# H3_eMMC.net
KiCad netlist of a schematic drawn in Altium Designer
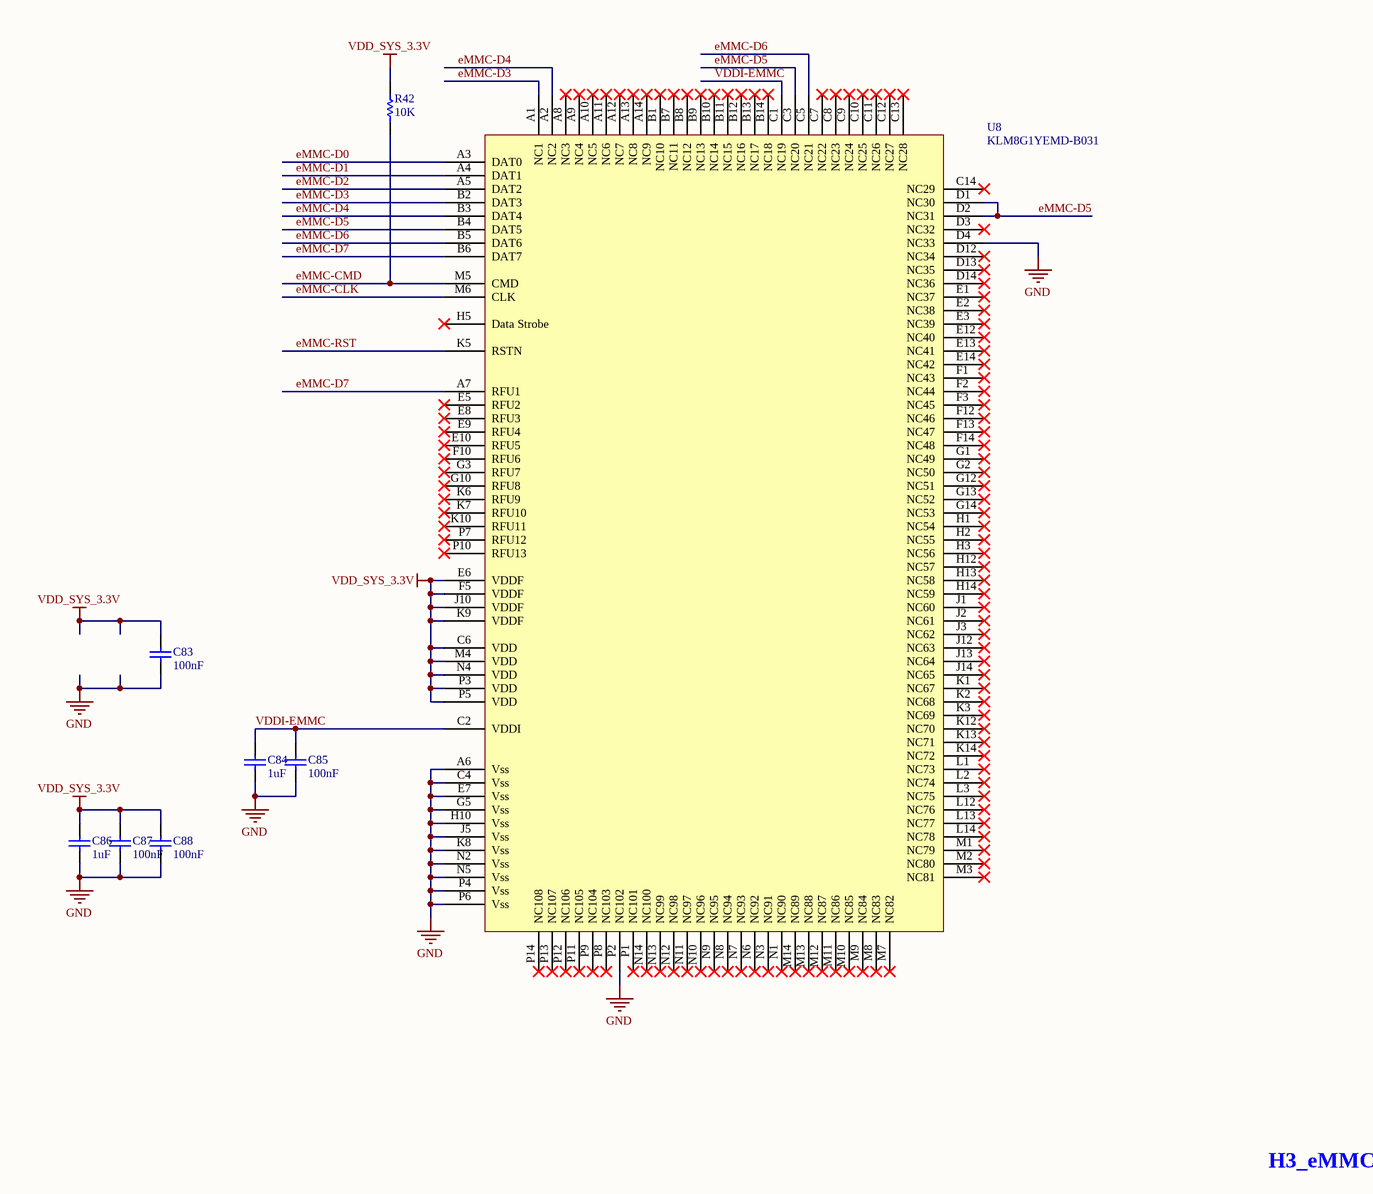
[diagram p0: H3_eMMC.SchDoc]

(export (version "E")
  (design (tool "Eeschema 10.0.6"))
  (components
    (comp (ref "C83")
      (value "100nF")
      (footprint "H3_Core:C0402")
      (description "电容")
      (fields (field (name "PUBLISHER") "Altium Limited"))
      (libsource (lib "Devices") (part "C0402"))
    )
    (comp (ref "C84")
      (value "1uF")
      (footprint "H3_Core:C0402")
      (description "电容")
      (fields (field (name "PUBLISHER") "Altium Limited"))
      (libsource (lib "Devices") (part "C0402"))
    )
    (comp (ref "C85")
      (value "100nF")
      (footprint "H3_Core:C0402")
      (description "电容")
      (fields (field (name "PUBLISHER") "Altium Limited"))
      (libsource (lib "Devices") (part "C0402"))
    )
    (comp (ref "C86")
      (value "1uF")
      (footprint "H3_Core:C0402")
      (description "电容")
      (fields (field (name "PUBLISHER") "Altium Limited"))
      (libsource (lib "Devices") (part "C0402"))
    )
    (comp (ref "C87")
      (value "100nF")
      (footprint "H3_Core:C0402")
      (description "电容")
      (fields (field (name "PUBLISHER") "Altium Limited"))
      (libsource (lib "Devices") (part "C0402"))
    )
    (comp (ref "C88")
      (value "100nF")
      (footprint "H3_Core:C0402")
      (description "电容")
      (fields (field (name "PUBLISHER") "Altium Limited"))
      (libsource (lib "Devices") (part "C0402"))
    )
    (comp (ref "R42")
      (value "10K")
      (footprint "H3_Core:R0402")
      (description "电阻")
      (fields (field (name "PUBLISHER") "Altium Limited"))
      (libsource (lib "Devices") (part "RES0402"))
    )
    (comp (ref "U8")
      (value "KLM8G1YEMD-B031")
      (footprint "H3_Core:FBGA153")
      (libsource (lib "IC") (part "KLM8G1YEMD-B031"))
    )
  )
  (nets
    (net (code "1") (name "/VDDI-EMMC") (class "Default")
      (node (ref "C84") (pin "2") (pinfunction "2_2") (pintype "passive"))
      (node (ref "C85") (pin "2") (pinfunction "2_2") (pintype "passive"))
      (node (ref "U8") (pin "C1") (pinfunction "NC19_C1") (pintype "passive"))
      (node (ref "U8") (pin "C2") (pinfunction "VDDI_C2") (pintype "passive"))
    )
    (net (code "2") (name "/eMMC-CLK") (class "Default")
      (node (ref "U8") (pin "M6") (pinfunction "CLK_M6") (pintype "passive"))
    )
    (net (code "3") (name "/eMMC-CMD") (class "Default")
      (node (ref "R42") (pin "1") (pinfunction "1_1") (pintype "passive"))
      (node (ref "U8") (pin "M5") (pinfunction "CMD_M5") (pintype "passive"))
    )
    (net (code "4") (name "/eMMC-D0") (class "Default")
      (node (ref "U8") (pin "A3") (pinfunction "DAT0_A3") (pintype "passive"))
    )
    (net (code "5") (name "/eMMC-D1") (class "Default")
      (node (ref "U8") (pin "A4") (pinfunction "DAT1_A4") (pintype "passive"))
    )
    (net (code "6") (name "/eMMC-D2") (class "Default")
      (node (ref "U8") (pin "A5") (pinfunction "DAT2_A5") (pintype "passive"))
    )
    (net (code "7") (name "/eMMC-D3") (class "Default")
      (node (ref "U8") (pin "A1") (pinfunction "NC1_A1") (pintype "passive"))
      (node (ref "U8") (pin "B2") (pinfunction "DAT3_B2") (pintype "passive"))
    )
    (net (code "8") (name "/eMMC-D4") (class "Default")
      (node (ref "U8") (pin "A2") (pinfunction "NC2_A2") (pintype "passive"))
      (node (ref "U8") (pin "B3") (pinfunction "DAT4_B3") (pintype "passive"))
    )
    (net (code "9") (name "/eMMC-D5") (class "Default")
      (node (ref "U8") (pin "B4") (pinfunction "DAT5_B4") (pintype "passive"))
      (node (ref "U8") (pin "C3") (pinfunction "NC20_C3") (pintype "passive"))
      (node (ref "U8") (pin "D1") (pinfunction "NC30_D1") (pintype "passive"))
      (node (ref "U8") (pin "D2") (pinfunction "NC31_D2") (pintype "passive"))
    )
    (net (code "10") (name "/eMMC-D6") (class "Default")
      (node (ref "U8") (pin "B5") (pinfunction "DAT6_B5") (pintype "passive"))
      (node (ref "U8") (pin "C5") (pinfunction "NC21_C5") (pintype "passive"))
    )
    (net (code "11") (name "/eMMC-D7") (class "Default")
      (node (ref "U8") (pin "A7") (pinfunction "RFU1_A7") (pintype "passive"))
      (node (ref "U8") (pin "B6") (pinfunction "DAT7_B6") (pintype "passive"))
    )
    (net (code "12") (name "/eMMC-RST") (class "Default")
      (node (ref "U8") (pin "K5") (pinfunction "RSTN_K5") (pintype "passive"))
    )
    (net (code "13") (name "GND") (class "Default")
      (node (ref "C83") (pin "1") (pinfunction "1_1") (pintype "passive"))
      (node (ref "C84") (pin "1") (pinfunction "1_1") (pintype "passive"))
      (node (ref "C85") (pin "1") (pinfunction "1_1") (pintype "passive"))
      (node (ref "C86") (pin "1") (pinfunction "1_1") (pintype "passive"))
      (node (ref "C87") (pin "1") (pinfunction "1_1") (pintype "passive"))
      (node (ref "C88") (pin "1") (pinfunction "1_1") (pintype "passive"))
      (node (ref "U8") (pin "A6") (pinfunction "Vss_A6") (pintype "passive"))
      (node (ref "U8") (pin "C4") (pinfunction "Vss_C4") (pintype "passive"))
      (node (ref "U8") (pin "D4") (pinfunction "NC33_D4") (pintype "passive"))
      (node (ref "U8") (pin "E7") (pinfunction "Vss_E7") (pintype "passive"))
      (node (ref "U8") (pin "G5") (pinfunction "Vss_G5") (pintype "passive"))
      (node (ref "U8") (pin "H10") (pinfunction "Vss_H10") (pintype "passive"))
      (node (ref "U8") (pin "J5") (pinfunction "Vss_J5") (pintype "passive"))
      (node (ref "U8") (pin "K8") (pinfunction "Vss_K8") (pintype "passive"))
      (node (ref "U8") (pin "N2") (pinfunction "Vss_N2") (pintype "passive"))
      (node (ref "U8") (pin "N5") (pinfunction "Vss_N5") (pintype "passive"))
      (node (ref "U8") (pin "P2") (pinfunction "NC102_P2") (pintype "passive"))
      (node (ref "U8") (pin "P4") (pinfunction "Vss_P4") (pintype "passive"))
      (node (ref "U8") (pin "P6") (pinfunction "Vss_P6") (pintype "passive"))
    )
    (net (code "14") (name "VDD_SYS_3.3V") (class "Default")
      (node (ref "C83") (pin "2") (pinfunction "2_2") (pintype "passive"))
      (node (ref "C86") (pin "2") (pinfunction "2_2") (pintype "passive"))
      (node (ref "C87") (pin "2") (pinfunction "2_2") (pintype "passive"))
      (node (ref "C88") (pin "2") (pinfunction "2_2") (pintype "passive"))
      (node (ref "R42") (pin "2") (pinfunction "2_2") (pintype "passive"))
      (node (ref "U8") (pin "C6") (pinfunction "VDD_C6") (pintype "passive"))
      (node (ref "U8") (pin "E6") (pinfunction "VDDF_E6") (pintype "passive"))
      (node (ref "U8") (pin "F5") (pinfunction "VDDF_F5") (pintype "passive"))
      (node (ref "U8") (pin "J10") (pinfunction "VDDF_J10") (pintype "passive"))
      (node (ref "U8") (pin "K9") (pinfunction "VDDF_K9") (pintype "passive"))
      (node (ref "U8") (pin "M4") (pinfunction "VDD_M4") (pintype "passive"))
      (node (ref "U8") (pin "N4") (pinfunction "VDD_N4") (pintype "passive"))
      (node (ref "U8") (pin "P3") (pinfunction "VDD_P3") (pintype "passive"))
      (node (ref "U8") (pin "P5") (pinfunction "VDD_P5") (pintype "passive"))
    )
    (net (code "15") (name "unconnected-(U8-Data_Strobe-PadH5)") (class "Default")
      (node (ref "U8") (pin "H5") (pinfunction "Data_Strobe_H5") (pintype "passive+no_connect"))
    )
    (net (code "16") (name "unconnected-(U8-NC3-PadA8)") (class "Default")
      (node (ref "U8") (pin "A8") (pinfunction "NC3_A8") (pintype "passive+no_connect"))
    )
    (net (code "17") (name "unconnected-(U8-NC4-PadA9)") (class "Default")
      (node (ref "U8") (pin "A9") (pinfunction "NC4_A9") (pintype "passive+no_connect"))
    )
    (net (code "18") (name "unconnected-(U8-NC5-PadA10)") (class "Default")
      (node (ref "U8") (pin "A10") (pinfunction "NC5_A10") (pintype "passive+no_connect"))
    )
    (net (code "19") (name "unconnected-(U8-NC6-PadA11)") (class "Default")
      (node (ref "U8") (pin "A11") (pinfunction "NC6_A11") (pintype "passive+no_connect"))
    )
    (net (code "20") (name "unconnected-(U8-NC7-PadA12)") (class "Default")
      (node (ref "U8") (pin "A12") (pinfunction "NC7_A12") (pintype "passive+no_connect"))
    )
    (net (code "21") (name "unconnected-(U8-NC8-PadA13)") (class "Default")
      (node (ref "U8") (pin "A13") (pinfunction "NC8_A13") (pintype "passive+no_connect"))
    )
    (net (code "22") (name "unconnected-(U8-NC9-PadA14)") (class "Default")
      (node (ref "U8") (pin "A14") (pinfunction "NC9_A14") (pintype "passive+no_connect"))
    )
    (net (code "23") (name "unconnected-(U8-NC10-PadB1)") (class "Default")
      (node (ref "U8") (pin "B1") (pinfunction "NC10_B1") (pintype "passive+no_connect"))
    )
    (net (code "24") (name "unconnected-(U8-NC11-PadB7)") (class "Default")
      (node (ref "U8") (pin "B7") (pinfunction "NC11_B7") (pintype "passive+no_connect"))
    )
    (net (code "25") (name "unconnected-(U8-NC12-PadB8)") (class "Default")
      (node (ref "U8") (pin "B8") (pinfunction "NC12_B8") (pintype "passive+no_connect"))
    )
    (net (code "26") (name "unconnected-(U8-NC13-PadB9)") (class "Default")
      (node (ref "U8") (pin "B9") (pinfunction "NC13_B9") (pintype "passive+no_connect"))
    )
    (net (code "27") (name "unconnected-(U8-NC14-PadB10)") (class "Default")
      (node (ref "U8") (pin "B10") (pinfunction "NC14_B10") (pintype "passive+no_connect"))
    )
    (net (code "28") (name "unconnected-(U8-NC15-PadB11)") (class "Default")
      (node (ref "U8") (pin "B11") (pinfunction "NC15_B11") (pintype "passive+no_connect"))
    )
    (net (code "29") (name "unconnected-(U8-NC16-PadB12)") (class "Default")
      (node (ref "U8") (pin "B12") (pinfunction "NC16_B12") (pintype "passive+no_connect"))
    )
    (net (code "30") (name "unconnected-(U8-NC17-PadB13)") (class "Default")
      (node (ref "U8") (pin "B13") (pinfunction "NC17_B13") (pintype "passive+no_connect"))
    )
    (net (code "31") (name "unconnected-(U8-NC18-PadB14)") (class "Default")
      (node (ref "U8") (pin "B14") (pinfunction "NC18_B14") (pintype "passive+no_connect"))
    )
    (net (code "32") (name "unconnected-(U8-NC22-PadC7)") (class "Default")
      (node (ref "U8") (pin "C7") (pinfunction "NC22_C7") (pintype "passive+no_connect"))
    )
    (net (code "33") (name "unconnected-(U8-NC23-PadC8)") (class "Default")
      (node (ref "U8") (pin "C8") (pinfunction "NC23_C8") (pintype "passive+no_connect"))
    )
    (net (code "34") (name "unconnected-(U8-NC24-PadC9)") (class "Default")
      (node (ref "U8") (pin "C9") (pinfunction "NC24_C9") (pintype "passive+no_connect"))
    )
    (net (code "35") (name "unconnected-(U8-NC25-PadC10)") (class "Default")
      (node (ref "U8") (pin "C10") (pinfunction "NC25_C10") (pintype "passive+no_connect"))
    )
    (net (code "36") (name "unconnected-(U8-NC26-PadC11)") (class "Default")
      (node (ref "U8") (pin "C11") (pinfunction "NC26_C11") (pintype "passive+no_connect"))
    )
    (net (code "37") (name "unconnected-(U8-NC27-PadC12)") (class "Default")
      (node (ref "U8") (pin "C12") (pinfunction "NC27_C12") (pintype "passive+no_connect"))
    )
    (net (code "38") (name "unconnected-(U8-NC28-PadC13)") (class "Default")
      (node (ref "U8") (pin "C13") (pinfunction "NC28_C13") (pintype "passive+no_connect"))
    )
    (net (code "39") (name "unconnected-(U8-NC29-PadC14)") (class "Default")
      (node (ref "U8") (pin "C14") (pinfunction "NC29_C14") (pintype "passive+no_connect"))
    )
    (net (code "40") (name "unconnected-(U8-NC32-PadD3)") (class "Default")
      (node (ref "U8") (pin "D3") (pinfunction "NC32_D3") (pintype "passive+no_connect"))
    )
    (net (code "41") (name "unconnected-(U8-NC34-PadD12)") (class "Default")
      (node (ref "U8") (pin "D12") (pinfunction "NC34_D12") (pintype "passive+no_connect"))
    )
    (net (code "42") (name "unconnected-(U8-NC35-PadD13)") (class "Default")
      (node (ref "U8") (pin "D13") (pinfunction "NC35_D13") (pintype "passive+no_connect"))
    )
    (net (code "43") (name "unconnected-(U8-NC36-PadD14)") (class "Default")
      (node (ref "U8") (pin "D14") (pinfunction "NC36_D14") (pintype "passive+no_connect"))
    )
    (net (code "44") (name "unconnected-(U8-NC37-PadE1)") (class "Default")
      (node (ref "U8") (pin "E1") (pinfunction "NC37_E1") (pintype "passive+no_connect"))
    )
    (net (code "45") (name "unconnected-(U8-NC38-PadE2)") (class "Default")
      (node (ref "U8") (pin "E2") (pinfunction "NC38_E2") (pintype "passive+no_connect"))
    )
    (net (code "46") (name "unconnected-(U8-NC39-PadE3)") (class "Default")
      (node (ref "U8") (pin "E3") (pinfunction "NC39_E3") (pintype "passive+no_connect"))
    )
    (net (code "47") (name "unconnected-(U8-NC40-PadE12)") (class "Default")
      (node (ref "U8") (pin "E12") (pinfunction "NC40_E12") (pintype "passive+no_connect"))
    )
    (net (code "48") (name "unconnected-(U8-NC41-PadE13)") (class "Default")
      (node (ref "U8") (pin "E13") (pinfunction "NC41_E13") (pintype "passive+no_connect"))
    )
    (net (code "49") (name "unconnected-(U8-NC42-PadE14)") (class "Default")
      (node (ref "U8") (pin "E14") (pinfunction "NC42_E14") (pintype "passive+no_connect"))
    )
    (net (code "50") (name "unconnected-(U8-NC43-PadF1)") (class "Default")
      (node (ref "U8") (pin "F1") (pinfunction "NC43_F1") (pintype "passive+no_connect"))
    )
    (net (code "51") (name "unconnected-(U8-NC44-PadF2)") (class "Default")
      (node (ref "U8") (pin "F2") (pinfunction "NC44_F2") (pintype "passive+no_connect"))
    )
    (net (code "52") (name "unconnected-(U8-NC45-PadF3)") (class "Default")
      (node (ref "U8") (pin "F3") (pinfunction "NC45_F3") (pintype "passive+no_connect"))
    )
    (net (code "53") (name "unconnected-(U8-NC46-PadF12)") (class "Default")
      (node (ref "U8") (pin "F12") (pinfunction "NC46_F12") (pintype "passive+no_connect"))
    )
    (net (code "54") (name "unconnected-(U8-NC47-PadF13)") (class "Default")
      (node (ref "U8") (pin "F13") (pinfunction "NC47_F13") (pintype "passive+no_connect"))
    )
    (net (code "55") (name "unconnected-(U8-NC48-PadF14)") (class "Default")
      (node (ref "U8") (pin "F14") (pinfunction "NC48_F14") (pintype "passive+no_connect"))
    )
    (net (code "56") (name "unconnected-(U8-NC49-PadG1)") (class "Default")
      (node (ref "U8") (pin "G1") (pinfunction "NC49_G1") (pintype "passive+no_connect"))
    )
    (net (code "57") (name "unconnected-(U8-NC50-PadG2)") (class "Default")
      (node (ref "U8") (pin "G2") (pinfunction "NC50_G2") (pintype "passive+no_connect"))
    )
    (net (code "58") (name "unconnected-(U8-NC51-PadG12)") (class "Default")
      (node (ref "U8") (pin "G12") (pinfunction "NC51_G12") (pintype "passive+no_connect"))
    )
    (net (code "59") (name "unconnected-(U8-NC52-PadG13)") (class "Default")
      (node (ref "U8") (pin "G13") (pinfunction "NC52_G13") (pintype "passive+no_connect"))
    )
    (net (code "60") (name "unconnected-(U8-NC53-PadG14)") (class "Default")
      (node (ref "U8") (pin "G14") (pinfunction "NC53_G14") (pintype "passive+no_connect"))
    )
    (net (code "61") (name "unconnected-(U8-NC54-PadH1)") (class "Default")
      (node (ref "U8") (pin "H1") (pinfunction "NC54_H1") (pintype "passive+no_connect"))
    )
    (net (code "62") (name "unconnected-(U8-NC55-PadH2)") (class "Default")
      (node (ref "U8") (pin "H2") (pinfunction "NC55_H2") (pintype "passive+no_connect"))
    )
    (net (code "63") (name "unconnected-(U8-NC56-PadH3)") (class "Default")
      (node (ref "U8") (pin "H3") (pinfunction "NC56_H3") (pintype "passive+no_connect"))
    )
    (net (code "64") (name "unconnected-(U8-NC57-PadH12)") (class "Default")
      (node (ref "U8") (pin "H12") (pinfunction "NC57_H12") (pintype "passive+no_connect"))
    )
    (net (code "65") (name "unconnected-(U8-NC58-PadH13)") (class "Default")
      (node (ref "U8") (pin "H13") (pinfunction "NC58_H13") (pintype "passive+no_connect"))
    )
    (net (code "66") (name "unconnected-(U8-NC59-PadH14)") (class "Default")
      (node (ref "U8") (pin "H14") (pinfunction "NC59_H14") (pintype "passive+no_connect"))
    )
    (net (code "67") (name "unconnected-(U8-NC60-PadJ1)") (class "Default")
      (node (ref "U8") (pin "J1") (pinfunction "NC60_J1") (pintype "passive+no_connect"))
    )
    (net (code "68") (name "unconnected-(U8-NC61-PadJ2)") (class "Default")
      (node (ref "U8") (pin "J2") (pinfunction "NC61_J2") (pintype "passive+no_connect"))
    )
    (net (code "69") (name "unconnected-(U8-NC62-PadJ3)") (class "Default")
      (node (ref "U8") (pin "J3") (pinfunction "NC62_J3") (pintype "passive+no_connect"))
    )
    (net (code "70") (name "unconnected-(U8-NC63-PadJ12)") (class "Default")
      (node (ref "U8") (pin "J12") (pinfunction "NC63_J12") (pintype "passive+no_connect"))
    )
    (net (code "71") (name "unconnected-(U8-NC64-PadJ13)") (class "Default")
      (node (ref "U8") (pin "J13") (pinfunction "NC64_J13") (pintype "passive+no_connect"))
    )
    (net (code "72") (name "unconnected-(U8-NC65-PadJ14)") (class "Default")
      (node (ref "U8") (pin "J14") (pinfunction "NC65_J14") (pintype "passive+no_connect"))
    )
    (net (code "73") (name "unconnected-(U8-NC67-PadK1)") (class "Default")
      (node (ref "U8") (pin "K1") (pinfunction "NC67_K1") (pintype "passive+no_connect"))
    )
    (net (code "74") (name "unconnected-(U8-NC68-PadK2)") (class "Default")
      (node (ref "U8") (pin "K2") (pinfunction "NC68_K2") (pintype "passive+no_connect"))
    )
    (net (code "75") (name "unconnected-(U8-NC69-PadK3)") (class "Default")
      (node (ref "U8") (pin "K3") (pinfunction "NC69_K3") (pintype "passive+no_connect"))
    )
    (net (code "76") (name "unconnected-(U8-NC70-PadK12)") (class "Default")
      (node (ref "U8") (pin "K12") (pinfunction "NC70_K12") (pintype "passive+no_connect"))
    )
    (net (code "77") (name "unconnected-(U8-NC71-PadK13)") (class "Default")
      (node (ref "U8") (pin "K13") (pinfunction "NC71_K13") (pintype "passive+no_connect"))
    )
    (net (code "78") (name "unconnected-(U8-NC72-PadK14)") (class "Default")
      (node (ref "U8") (pin "K14") (pinfunction "NC72_K14") (pintype "passive+no_connect"))
    )
    (net (code "79") (name "unconnected-(U8-NC73-PadL1)") (class "Default")
      (node (ref "U8") (pin "L1") (pinfunction "NC73_L1") (pintype "passive+no_connect"))
    )
    (net (code "80") (name "unconnected-(U8-NC74-PadL2)") (class "Default")
      (node (ref "U8") (pin "L2") (pinfunction "NC74_L2") (pintype "passive+no_connect"))
    )
    (net (code "81") (name "unconnected-(U8-NC75-PadL3)") (class "Default")
      (node (ref "U8") (pin "L3") (pinfunction "NC75_L3") (pintype "passive+no_connect"))
    )
    (net (code "82") (name "unconnected-(U8-NC76-PadL12)") (class "Default")
      (node (ref "U8") (pin "L12") (pinfunction "NC76_L12") (pintype "passive+no_connect"))
    )
    (net (code "83") (name "unconnected-(U8-NC77-PadL13)") (class "Default")
      (node (ref "U8") (pin "L13") (pinfunction "NC77_L13") (pintype "passive+no_connect"))
    )
    (net (code "84") (name "unconnected-(U8-NC78-PadL14)") (class "Default")
      (node (ref "U8") (pin "L14") (pinfunction "NC78_L14") (pintype "passive+no_connect"))
    )
    (net (code "85") (name "unconnected-(U8-NC79-PadM1)") (class "Default")
      (node (ref "U8") (pin "M1") (pinfunction "NC79_M1") (pintype "passive+no_connect"))
    )
    (net (code "86") (name "unconnected-(U8-NC80-PadM2)") (class "Default")
      (node (ref "U8") (pin "M2") (pinfunction "NC80_M2") (pintype "passive+no_connect"))
    )
    (net (code "87") (name "unconnected-(U8-NC81-PadM3)") (class "Default")
      (node (ref "U8") (pin "M3") (pinfunction "NC81_M3") (pintype "passive+no_connect"))
    )
    (net (code "88") (name "unconnected-(U8-NC82-PadM7)") (class "Default")
      (node (ref "U8") (pin "M7") (pinfunction "NC82_M7") (pintype "passive+no_connect"))
    )
    (net (code "89") (name "unconnected-(U8-NC83-PadM8)") (class "Default")
      (node (ref "U8") (pin "M8") (pinfunction "NC83_M8") (pintype "passive+no_connect"))
    )
    (net (code "90") (name "unconnected-(U8-NC84-PadM9)") (class "Default")
      (node (ref "U8") (pin "M9") (pinfunction "NC84_M9") (pintype "passive+no_connect"))
    )
    (net (code "91") (name "unconnected-(U8-NC85-PadM10)") (class "Default")
      (node (ref "U8") (pin "M10") (pinfunction "NC85_M10") (pintype "passive+no_connect"))
    )
    (net (code "92") (name "unconnected-(U8-NC86-PadM11)") (class "Default")
      (node (ref "U8") (pin "M11") (pinfunction "NC86_M11") (pintype "passive+no_connect"))
    )
    (net (code "93") (name "unconnected-(U8-NC87-PadM12)") (class "Default")
      (node (ref "U8") (pin "M12") (pinfunction "NC87_M12") (pintype "passive+no_connect"))
    )
    (net (code "94") (name "unconnected-(U8-NC88-PadM13)") (class "Default")
      (node (ref "U8") (pin "M13") (pinfunction "NC88_M13") (pintype "passive+no_connect"))
    )
    (net (code "95") (name "unconnected-(U8-NC89-PadM14)") (class "Default")
      (node (ref "U8") (pin "M14") (pinfunction "NC89_M14") (pintype "passive+no_connect"))
    )
    (net (code "96") (name "unconnected-(U8-NC90-PadN1)") (class "Default")
      (node (ref "U8") (pin "N1") (pinfunction "NC90_N1") (pintype "passive+no_connect"))
    )
    (net (code "97") (name "unconnected-(U8-NC91-PadN3)") (class "Default")
      (node (ref "U8") (pin "N3") (pinfunction "NC91_N3") (pintype "passive+no_connect"))
    )
    (net (code "98") (name "unconnected-(U8-NC92-PadN6)") (class "Default")
      (node (ref "U8") (pin "N6") (pinfunction "NC92_N6") (pintype "passive+no_connect"))
    )
    (net (code "99") (name "unconnected-(U8-NC93-PadN7)") (class "Default")
      (node (ref "U8") (pin "N7") (pinfunction "NC93_N7") (pintype "passive+no_connect"))
    )
    (net (code "100") (name "unconnected-(U8-NC94-PadN8)") (class "Default")
      (node (ref "U8") (pin "N8") (pinfunction "NC94_N8") (pintype "passive+no_connect"))
    )
    (net (code "101") (name "unconnected-(U8-NC95-PadN9)") (class "Default")
      (node (ref "U8") (pin "N9") (pinfunction "NC95_N9") (pintype "passive+no_connect"))
    )
    (net (code "102") (name "unconnected-(U8-NC96-PadN10)") (class "Default")
      (node (ref "U8") (pin "N10") (pinfunction "NC96_N10") (pintype "passive+no_connect"))
    )
    (net (code "103") (name "unconnected-(U8-NC97-PadN11)") (class "Default")
      (node (ref "U8") (pin "N11") (pinfunction "NC97_N11") (pintype "passive+no_connect"))
    )
    (net (code "104") (name "unconnected-(U8-NC98-PadN12)") (class "Default")
      (node (ref "U8") (pin "N12") (pinfunction "NC98_N12") (pintype "passive+no_connect"))
    )
    (net (code "105") (name "unconnected-(U8-NC99-PadN13)") (class "Default")
      (node (ref "U8") (pin "N13") (pinfunction "NC99_N13") (pintype "passive+no_connect"))
    )
    (net (code "106") (name "unconnected-(U8-NC100-PadN14)") (class "Default")
      (node (ref "U8") (pin "N14") (pinfunction "NC100_N14") (pintype "passive+no_connect"))
    )
    (net (code "107") (name "unconnected-(U8-NC101-PadP1)") (class "Default")
      (node (ref "U8") (pin "P1") (pinfunction "NC101_P1") (pintype "passive+no_connect"))
    )
    (net (code "108") (name "unconnected-(U8-NC103-PadP8)") (class "Default")
      (node (ref "U8") (pin "P8") (pinfunction "NC103_P8") (pintype "passive+no_connect"))
    )
    (net (code "109") (name "unconnected-(U8-NC104-PadP9)") (class "Default")
      (node (ref "U8") (pin "P9") (pinfunction "NC104_P9") (pintype "passive+no_connect"))
    )
    (net (code "110") (name "unconnected-(U8-NC105-PadP11)") (class "Default")
      (node (ref "U8") (pin "P11") (pinfunction "NC105_P11") (pintype "passive+no_connect"))
    )
    (net (code "111") (name "unconnected-(U8-NC106-PadP12)") (class "Default")
      (node (ref "U8") (pin "P12") (pinfunction "NC106_P12") (pintype "passive+no_connect"))
    )
    (net (code "112") (name "unconnected-(U8-NC107-PadP13)") (class "Default")
      (node (ref "U8") (pin "P13") (pinfunction "NC107_P13") (pintype "passive+no_connect"))
    )
    (net (code "113") (name "unconnected-(U8-NC108-PadP14)") (class "Default")
      (node (ref "U8") (pin "P14") (pinfunction "NC108_P14") (pintype "passive+no_connect"))
    )
    (net (code "114") (name "unconnected-(U8-RFU2-PadE5)") (class "Default")
      (node (ref "U8") (pin "E5") (pinfunction "RFU2_E5") (pintype "passive+no_connect"))
    )
    (net (code "115") (name "unconnected-(U8-RFU3-PadE8)") (class "Default")
      (node (ref "U8") (pin "E8") (pinfunction "RFU3_E8") (pintype "passive+no_connect"))
    )
    (net (code "116") (name "unconnected-(U8-RFU4-PadE9)") (class "Default")
      (node (ref "U8") (pin "E9") (pinfunction "RFU4_E9") (pintype "passive+no_connect"))
    )
    (net (code "117") (name "unconnected-(U8-RFU5-PadE10)") (class "Default")
      (node (ref "U8") (pin "E10") (pinfunction "RFU5_E10") (pintype "passive+no_connect"))
    )
    (net (code "118") (name "unconnected-(U8-RFU6-PadF10)") (class "Default")
      (node (ref "U8") (pin "F10") (pinfunction "RFU6_F10") (pintype "passive+no_connect"))
    )
    (net (code "119") (name "unconnected-(U8-RFU7-PadG3)") (class "Default")
      (node (ref "U8") (pin "G3") (pinfunction "RFU7_G3") (pintype "passive+no_connect"))
    )
    (net (code "120") (name "unconnected-(U8-RFU8-PadG10)") (class "Default")
      (node (ref "U8") (pin "G10") (pinfunction "RFU8_G10") (pintype "passive+no_connect"))
    )
    (net (code "121") (name "unconnected-(U8-RFU9-PadK6)") (class "Default")
      (node (ref "U8") (pin "K6") (pinfunction "RFU9_K6") (pintype "passive+no_connect"))
    )
    (net (code "122") (name "unconnected-(U8-RFU10-PadK7)") (class "Default")
      (node (ref "U8") (pin "K7") (pinfunction "RFU10_K7") (pintype "passive+no_connect"))
    )
    (net (code "123") (name "unconnected-(U8-RFU11-PadK10)") (class "Default")
      (node (ref "U8") (pin "K10") (pinfunction "RFU11_K10") (pintype "passive+no_connect"))
    )
    (net (code "124") (name "unconnected-(U8-RFU12-PadP7)") (class "Default")
      (node (ref "U8") (pin "P7") (pinfunction "RFU12_P7") (pintype "passive+no_connect"))
    )
    (net (code "125") (name "unconnected-(U8-RFU13-PadP10)") (class "Default")
      (node (ref "U8") (pin "P10") (pinfunction "RFU13_P10") (pintype "passive+no_connect"))
    )
  )
)
